# Bomba_Agua.net
KiCad netlist of a schematic drawn in Altium Designer
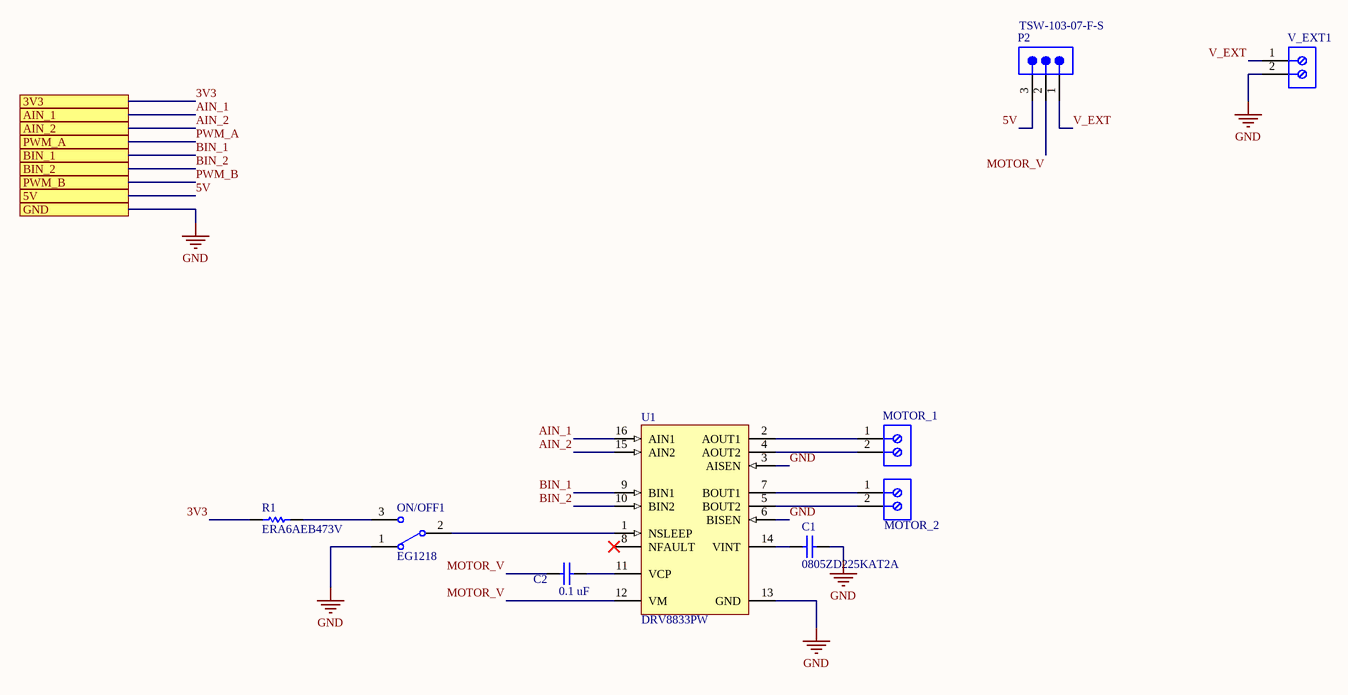
[diagram p0: Bomba_Agua.SchDoc]

(export (version "E")
  (design (tool "Eeschema 10.0.6"))
  (components
    (comp (ref "C1")
      (value "0805ZD225KAT2A")
      (footprint "CAPC2013X140X50ML20T25")
      (description "Chip Capacitor, 2.2 uF, +/- 10%, 10 V, -55 to 85 degC, 0805 (2012 Metric), RoHS, Tape and Reel")
      (fields (field (name "MANUFACTURER") "AVX"))
      (libsource (lib "Altium Content Vault") (part "CAP-NP-2"))
    )
    (comp (ref "C2")
      (value "0.1 uF")
      (footprint "CAPC2013X94X50ML20T25")
      (description "Chip Capacitor, Ceramic, 0.1 uF, 10%, 50 V, 0805, RoHS, Tape and Reel")
      (fields (field (name "MANUFACTURER") "AVX"))
      (libsource (lib "Altium Content Vault") (part "CAP-NP-2"))
    )
    (comp (ref "MOTOR_1")
      (value "691214110002")
      (footprint "691214110002")
      (description "Serie 2141 - 3.50 mm Horizontal Entry Modular with Rising Cage Clamp WR-TBL, 2 pin")
      (fields (field (name "MANUFACTURER") "Wurth Elektronik") (field (name "PUBLISHER") "WurthElektronik"))
      (libsource (lib "Altium Content Vault") (part "WE-CN-1P-F-TB2"))
    )
    (comp (ref "MOTOR_2")
      (value "691214110002")
      (footprint "691214110002")
      (description "Serie 2141 - 3.50 mm Horizontal Entry Modular with Rising Cage Clamp WR-TBL, 2 pin")
      (fields (field (name "MANUFACTURER") "Wurth Elektronik") (field (name "PUBLISHER") "WurthElektronik"))
      (libsource (lib "Altium Content Vault") (part "WE-CN-1P-F-TB2"))
    )
    (comp (ref "ON/OFF1")
      (value "EG1218")
      (footprint "ESWI-EG1218_V")
      (description "Slide Switch, 500 V, -20 to 70 degC, 3-Pin THD, RoHS")
      (libsource (lib "Altium Content Vault") (part "SW-SPDT-3_B"))
    )
    (comp (ref "P2")
      (value "TSW-103-07-F-S")
      (footprint "SMTC-TSW-103-07-X-S")
      (description "0.025\" SQ Post Header, Through-hole, Vertical, -55 to 125 degC, 2.54 mm Pitch, 3-Pin, Male, RoHS")
      (fields (field (name "MANUFACTURER") "Samtec"))
      (libsource (lib "Altium Content Vault") (part "SMTC-TSW-103-X-X-S-X"))
    )
    (comp (ref "R1")
      (value "ERA6AEB473V")
      (footprint "RESC2013X60X40ML20T25")
      (fields (field (name "MANUFACTURER") "Panasonic"))
      (libsource (lib "Altium Content Vault") (part "RES"))
    )
    (comp (ref "U1")
      (value "DRV8833PW")
      (footprint "PW0016A_M")
      (fields (field (name "MANUFACTURER") "Texas Instruments"))
      (libsource (lib "Altium Content Vault") (part "TI-DRV8833PW-16"))
    )
    (comp (ref "V_EXT1")
      (value "691214110002")
      (footprint "691214110002")
      (description "Serie 2141 - 3.50 mm Horizontal Entry Modular with Rising Cage Clamp WR-TBL, 2 pin")
      (fields (field (name "MANUFACTURER") "Wurth Elektronik") (field (name "PUBLISHER") "WurthElektronik"))
      (libsource (lib "Altium Content Vault") (part "WE-CN-1P-F-TB2"))
    )
  )
  (nets
    (net (code "1") (name "/3V3") (class "Default")
      (node (ref "R1") (pin "2") (pinfunction "2_2") (pintype "passive"))
    )
    (net (code "2") (name "/5V") (class "Default")
      (node (ref "P2") (pin "3") (pinfunction "3_3") (pintype "passive"))
    )
    (net (code "3") (name "/AIN_1") (class "Default")
      (node (ref "U1") (pin "16") (pinfunction "AIN1_16") (pintype "input"))
    )
    (net (code "4") (name "/AIN_2") (class "Default")
      (node (ref "U1") (pin "15") (pinfunction "AIN2_15") (pintype "input"))
    )
    (net (code "5") (name "/BIN_1") (class "Default")
      (node (ref "U1") (pin "9") (pinfunction "BIN1_9") (pintype "input"))
    )
    (net (code "6") (name "/BIN_2") (class "Default")
      (node (ref "U1") (pin "10") (pinfunction "BIN2_10") (pintype "input"))
    )
    (net (code "7") (name "/MOTOR_V") (class "Default")
      (node (ref "C2") (pin "2") (pinfunction "2_2") (pintype "passive"))
      (node (ref "P2") (pin "2") (pinfunction "2_2") (pintype "passive"))
      (node (ref "U1") (pin "12") (pinfunction "VM_12") (pintype "power_in"))
    )
    (net (code "10") (name "/V_EXT") (class "Default")
      (node (ref "P2") (pin "1") (pinfunction "1_1") (pintype "passive"))
      (node (ref "V_EXT1") (pin "1") (pinfunction "1_1") (pintype "passive"))
    )
    (net (code "11") (name "GND") (class "Default")
      (node (ref "C1") (pin "2") (pinfunction "2_2") (pintype "passive"))
      (node (ref "ON/OFF1") (pin "1") (pinfunction "1_1") (pintype "passive"))
      (node (ref "U1") (pin "13") (pinfunction "GND_13") (pintype "power_in"))
      (node (ref "U1") (pin "3") (pinfunction "AISEN_3") (pintype "input"))
      (node (ref "U1") (pin "6") (pinfunction "BISEN_6") (pintype "input"))
      (node (ref "V_EXT1") (pin "2") (pinfunction "2_2") (pintype "passive"))
    )
    (net (code "12") (name "Net-(ON/OFF1-COM)") (class "Default")
      (node (ref "ON/OFF1") (pin "2") (pinfunction "COM_2") (pintype "passive"))
      (node (ref "U1") (pin "1") (pinfunction "NSLEEP_1") (pintype "input"))
    )
    (net (code "13") (name "Net-(ON/OFF1-Pad3)") (class "Default")
      (node (ref "ON/OFF1") (pin "3") (pinfunction "3_3") (pintype "passive"))
      (node (ref "R1") (pin "1") (pinfunction "1_1") (pintype "passive"))
    )
    (net (code "14") (name "Net-(U1-AOUT1)") (class "Default")
      (node (ref "MOTOR_1") (pin "1") (pinfunction "1_1") (pintype "passive"))
      (node (ref "U1") (pin "2") (pinfunction "AOUT1_2") (pintype "tri_state"))
    )
    (net (code "15") (name "Net-(U1-AOUT2)") (class "Default")
      (node (ref "MOTOR_1") (pin "2") (pinfunction "2_2") (pintype "passive"))
      (node (ref "U1") (pin "4") (pinfunction "AOUT2_4") (pintype "tri_state"))
    )
    (net (code "16") (name "Net-(U1-BOUT1)") (class "Default")
      (node (ref "MOTOR_2") (pin "1") (pinfunction "1_1") (pintype "passive"))
      (node (ref "U1") (pin "7") (pinfunction "BOUT1_7") (pintype "tri_state"))
    )
    (net (code "17") (name "Net-(U1-BOUT2)") (class "Default")
      (node (ref "MOTOR_2") (pin "2") (pinfunction "2_2") (pintype "passive"))
      (node (ref "U1") (pin "5") (pinfunction "BOUT2_5") (pintype "tri_state"))
    )
    (net (code "18") (name "Net-(U1-VCP)") (class "Default")
      (node (ref "C2") (pin "1") (pinfunction "1_1") (pintype "passive"))
      (node (ref "U1") (pin "11") (pinfunction "VCP_11") (pintype "passive"))
    )
    (net (code "19") (name "Net-(U1-VINT)") (class "Default")
      (node (ref "C1") (pin "1") (pinfunction "1_1") (pintype "passive"))
      (node (ref "U1") (pin "14") (pinfunction "VINT_14") (pintype "passive"))
    )
    (net (code "20") (name "unconnected-(U1-NFAULT-Pad8)") (class "Default")
      (node (ref "U1") (pin "8") (pinfunction "NFAULT_8") (pintype "open_collector+no_connect"))
    )
  )
)
